# RFM232_probe.net
KiCad netlist of a schematic drawn in Altium Designer
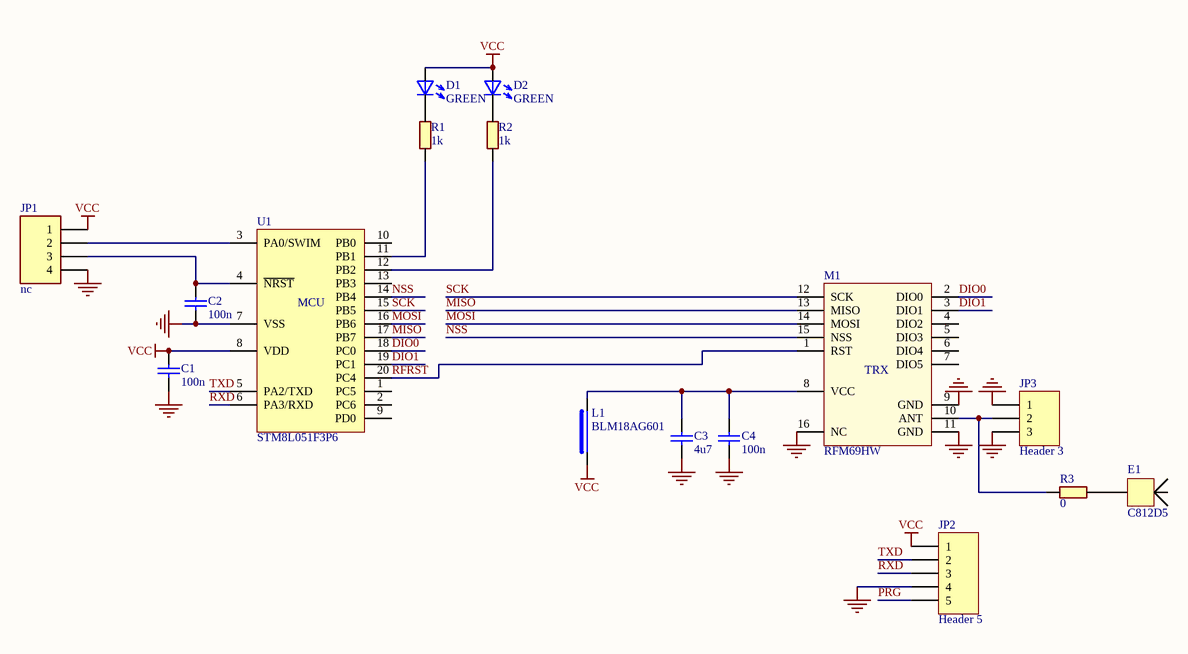
[diagram p0: RFM232_probe.SchDoc]

(export (version "E")
  (design (tool "Eeschema 10.0.6"))
  (components
    (comp (ref "C1") (value "100n") (footprint "CAPC1608X08N") (libsource (lib "Discrete") (part "CAPN")))
    (comp (ref "C2") (value "100n") (footprint "CAPC1608X08N") (libsource (lib "Discrete") (part "CAPN")))
    (comp (ref "C3") (value "4u7") (footprint "CAPC2012X11N") (libsource (lib "Discrete") (part "CAPN")))
    (comp (ref "C4") (value "100n") (footprint "CAPC1608X08N") (libsource (lib "Discrete") (part "CAPN")))
    (comp (ref "D1")
      (value "GREEN")
      (footprint "LEDC200X125X80L40N")
      (libsource (lib "Discrete") (part "DLED"))
    )
    (comp (ref "D2")
      (value "GREEN")
      (footprint "LEDC200X125X80L40N")
      (libsource (lib "Discrete") (part "DLED"))
    )
    (comp (ref "E1") (value "C812D5") (footprint "C812D5") (libsource (lib "RFUART") (part "C812D5")))
    (comp (ref "JP1")
      (value "nc")
      (footprint "HDRV4W70P254_4X1_889X254H754")
      (description "4 Pin Header 2,0 mm, 1x04")
      (libsource (lib "e4") (part "HEADER 4"))
    )
    (comp (ref "JP2")
      (value "Header 5")
      (footprint "HDRV5W70P254_5X1_1143X254H754")
      (description "Header, 5-Pin")
      (fields (field (name "PUBLISHER") "Altium Limited"))
      (libsource (lib "Miscellaneous Connectors") (part "Header 5"))
    )
    (comp (ref "JP3")
      (value "Header 3")
      (footprint "HDRV3W70P254_3X1_635X254H754")
      (description "Header, 3-Pin")
      (fields (field (name "PUBLISHER") "Altium Limited"))
      (libsource (lib "Miscellaneous Connectors") (part "Header 3"))
    )
    (comp (ref "L1")
      (value "BLM18AG601")
      (footprint "INDC1608X10N")
      (libsource (lib "Discrete") (part "SUPRESOR"))
    )
    (comp (ref "M1")
      (value "RFM69HW")
      (footprint "LGA16_RFM69")
      (libsource (lib "CLAP_M505_WL_BP_V22") (part "RFM69HW_V13_2"))
    )
    (comp (ref "R1") (value "1k") (footprint "RESC1608X06N") (libsource (lib "Discrete") (part "RES")))
    (comp (ref "R2") (value "1k") (footprint "RESC1608X06N") (libsource (lib "Discrete") (part "RES")))
    (comp (ref "R3") (value "0") (footprint "RESC2012X07N") (libsource (lib "") (part "RES_1")))
    (comp (ref "U1")
      (value "STM8L051F3P6")
      (footprint "TSOP65P640X110-20N")
      (libsource (lib "reedswitch_stm8l") (part "STM8L051F3P6"))
    )
  )
  (nets
    (net (code "1") (name "/DIO0") (class "Default")
      (node (ref "M1") (pin "2") (pinfunction "DIO0_2") (pintype "passive"))
      (node (ref "U1") (pin "18") (pinfunction "PC0_18") (pintype "passive"))
    )
    (net (code "2") (name "/DIO1") (class "Default")
      (node (ref "M1") (pin "3") (pinfunction "DIO1_3") (pintype "passive"))
      (node (ref "U1") (pin "19") (pinfunction "PC1_19") (pintype "passive"))
    )
    (net (code "3") (name "/MISO") (class "Default")
      (node (ref "M1") (pin "13") (pinfunction "MISO_13") (pintype "passive"))
      (node (ref "U1") (pin "17") (pinfunction "PB7_17") (pintype "passive"))
    )
    (net (code "4") (name "/MOSI") (class "Default")
      (node (ref "M1") (pin "14") (pinfunction "MOSI_14") (pintype "passive"))
      (node (ref "U1") (pin "16") (pinfunction "PB6_16") (pintype "passive"))
    )
    (net (code "5") (name "/NSS") (class "Default")
      (node (ref "M1") (pin "15") (pinfunction "NSS_15") (pintype "passive"))
      (node (ref "U1") (pin "14") (pinfunction "PB4_14") (pintype "passive"))
    )
    (net (code "6") (name "/PRG") (class "Default")
      (node (ref "JP2") (pin "5") (pinfunction "5_5") (pintype "passive"))
    )
    (net (code "7") (name "/RFRST") (class "Default")
      (node (ref "M1") (pin "1") (pinfunction "RST_1") (pintype "passive"))
      (node (ref "U1") (pin "20") (pinfunction "PC4_20") (pintype "passive"))
    )
    (net (code "8") (name "/RXD") (class "Default")
      (node (ref "JP2") (pin "3") (pinfunction "3_3") (pintype "passive"))
      (node (ref "U1") (pin "6") (pinfunction "PA3/RXD_6") (pintype "passive"))
    )
    (net (code "9") (name "/SCK") (class "Default")
      (node (ref "M1") (pin "12") (pinfunction "SCK_12") (pintype "passive"))
      (node (ref "U1") (pin "15") (pinfunction "PB5_15") (pintype "passive"))
    )
    (net (code "10") (name "/TXD") (class "Default")
      (node (ref "JP2") (pin "2") (pinfunction "2_2") (pintype "passive"))
      (node (ref "U1") (pin "5") (pinfunction "PA2/TXD_5") (pintype "passive"))
    )
    (net (code "11") (name "GND") (class "Default")
      (node (ref "C1") (pin "2") (pinfunction "2_2") (pintype "passive"))
      (node (ref "C2") (pin "2") (pinfunction "2_2") (pintype "passive"))
      (node (ref "C3") (pin "2") (pinfunction "2_2") (pintype "passive"))
      (node (ref "C4") (pin "2") (pinfunction "2_2") (pintype "passive"))
      (node (ref "JP1") (pin "4") (pinfunction "4_4") (pintype "passive"))
      (node (ref "JP2") (pin "4") (pinfunction "4_4") (pintype "passive"))
      (node (ref "JP3") (pin "1") (pinfunction "1_1") (pintype "passive"))
      (node (ref "JP3") (pin "3") (pinfunction "3_3") (pintype "passive"))
      (node (ref "M1") (pin "11") (pinfunction "GND_11") (pintype "passive"))
      (node (ref "M1") (pin "16") (pinfunction "NC_16") (pintype "passive"))
      (node (ref "M1") (pin "9") (pinfunction "GND_9") (pintype "passive"))
      (node (ref "U1") (pin "7") (pinfunction "VSS_7") (pintype "passive"))
    )
    (net (code "12") (name "Net-(D1-2)") (class "Default")
      (node (ref "D1") (pin "K") (pinfunction "2_K") (pintype "passive"))
      (node (ref "R1") (pin "1") (pinfunction "1_1") (pintype "passive"))
    )
    (net (code "13") (name "Net-(D2-2)") (class "Default")
      (node (ref "D2") (pin "K") (pinfunction "2_K") (pintype "passive"))
      (node (ref "R2") (pin "1") (pinfunction "1_1") (pintype "passive"))
    )
    (net (code "14") (name "Net-(E1-IN)") (class "Default")
      (node (ref "E1") (pin "1") (pinfunction "IN_1") (pintype "passive"))
      (node (ref "R3") (pin "2") (pinfunction "2_2") (pintype "passive"))
    )
    (net (code "15") (name "Net-(M1-ANT)") (class "Default")
      (node (ref "JP3") (pin "2") (pinfunction "2_2") (pintype "passive"))
      (node (ref "M1") (pin "10") (pinfunction "ANT_10") (pintype "passive"))
      (node (ref "R3") (pin "1") (pinfunction "1_1") (pintype "passive"))
    )
    (net (code "16") (name "Net-(M1-VCC)") (class "Default")
      (node (ref "C3") (pin "1") (pinfunction "1_1") (pintype "passive"))
      (node (ref "C4") (pin "1") (pinfunction "1_1") (pintype "passive"))
      (node (ref "L1") (pin "2") (pinfunction "2_2") (pintype "passive"))
      (node (ref "M1") (pin "8") (pinfunction "VCC_8") (pintype "passive"))
    )
    (net (code "17") (name "Net-(U1-PA0{slash}SWIM)") (class "Default")
      (node (ref "JP1") (pin "2") (pinfunction "2_2") (pintype "passive"))
      (node (ref "U1") (pin "3") (pinfunction "PA0/SWIM_3") (pintype "passive"))
    )
    (net (code "18") (name "Net-(U1-PB1)") (class "Default")
      (node (ref "R1") (pin "2") (pinfunction "2_2") (pintype "passive"))
      (node (ref "U1") (pin "11") (pinfunction "PB1_11") (pintype "passive"))
    )
    (net (code "19") (name "Net-(U1-PB2)") (class "Default")
      (node (ref "R2") (pin "2") (pinfunction "2_2") (pintype "passive"))
      (node (ref "U1") (pin "12") (pinfunction "PB2_12") (pintype "passive"))
    )
    (net (code "20") (name "Net-(U1-~{NRST})") (class "Default")
      (node (ref "C2") (pin "1") (pinfunction "1_1") (pintype "passive"))
      (node (ref "JP1") (pin "3") (pinfunction "3_3") (pintype "passive"))
      (node (ref "U1") (pin "4") (pinfunction "~{NRST}_4") (pintype "passive"))
    )
    (net (code "21") (name "VCC") (class "Default")
      (node (ref "C1") (pin "1") (pinfunction "1_1") (pintype "passive"))
      (node (ref "D1") (pin "A") (pinfunction "1_A") (pintype "passive"))
      (node (ref "D2") (pin "A") (pinfunction "1_A") (pintype "passive"))
      (node (ref "JP1") (pin "1") (pinfunction "1_1") (pintype "passive"))
      (node (ref "JP2") (pin "1") (pinfunction "1_1") (pintype "passive"))
      (node (ref "L1") (pin "1") (pinfunction "1_1") (pintype "passive"))
      (node (ref "U1") (pin "8") (pinfunction "VDD_8") (pintype "passive"))
    )
    (net (code "22") (name "unconnected-(M1-DIO2-Pad4)") (class "Default")
      (node (ref "M1") (pin "4") (pinfunction "DIO2_4") (pintype "passive"))
    )
    (net (code "23") (name "unconnected-(M1-DIO3-Pad5)") (class "Default")
      (node (ref "M1") (pin "5") (pinfunction "DIO3_5") (pintype "passive"))
    )
    (net (code "24") (name "unconnected-(M1-DIO4-Pad6)") (class "Default")
      (node (ref "M1") (pin "6") (pinfunction "DIO4_6") (pintype "passive"))
    )
    (net (code "25") (name "unconnected-(M1-DIO5-Pad7)") (class "Default")
      (node (ref "M1") (pin "7") (pinfunction "DIO5_7") (pintype "passive"))
    )
    (net (code "26") (name "unconnected-(U1-PB0-Pad10)") (class "Default")
      (node (ref "U1") (pin "10") (pinfunction "PB0_10") (pintype "passive"))
    )
    (net (code "27") (name "unconnected-(U1-PB3-Pad13)") (class "Default")
      (node (ref "U1") (pin "13") (pinfunction "PB3_13") (pintype "passive"))
    )
    (net (code "28") (name "unconnected-(U1-PC5-Pad1)") (class "Default")
      (node (ref "U1") (pin "1") (pinfunction "PC5_1") (pintype "passive"))
    )
    (net (code "29") (name "unconnected-(U1-PC6-Pad2)") (class "Default")
      (node (ref "U1") (pin "2") (pinfunction "PC6_2") (pintype "passive"))
    )
    (net (code "30") (name "unconnected-(U1-PD0-Pad9)") (class "Default")
      (node (ref "U1") (pin "9") (pinfunction "PD0_9") (pintype "passive"))
    )
  )
)
